# UI_Adapter.net
KiCad netlist of a schematic drawn in EAGLE
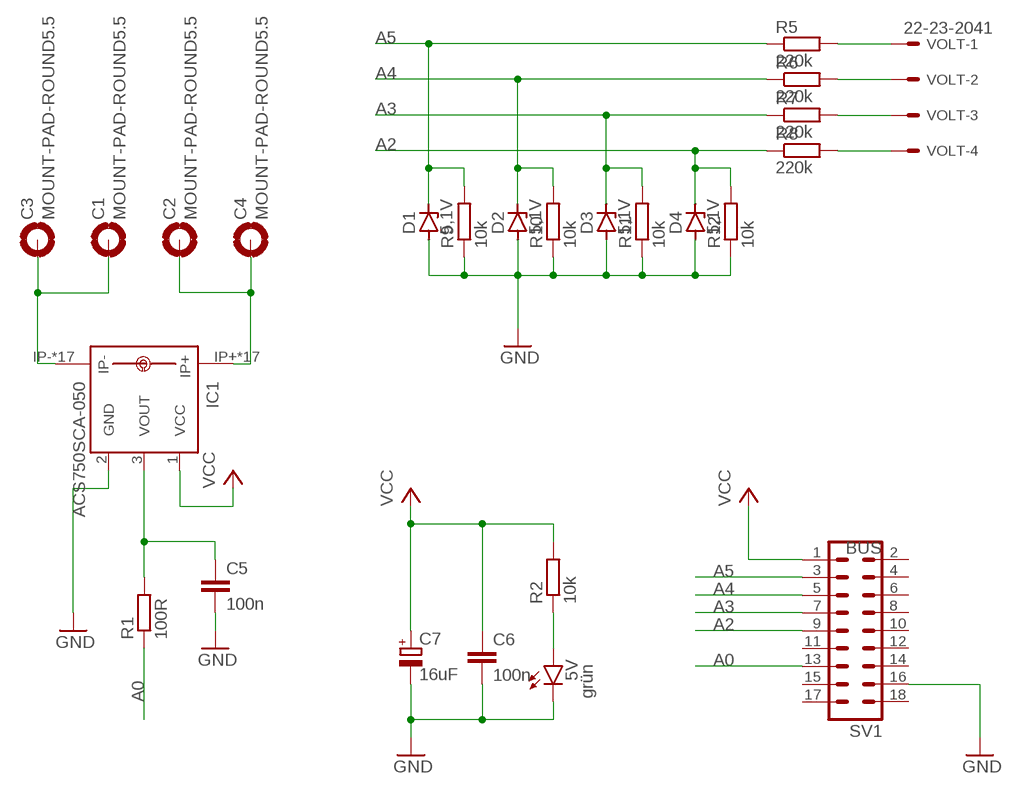
[diagram p0: schematic, sheet 1]

(export (version "E")
  (design (tool "Eeschema 10.0.6"))
  (components
    (comp (ref "5V")
      (value "grün")
      (footprint "eagle-import:LED3MM")
      (libsource (lib "eagle-import") (part "LED3MM"))
    )
    (comp (ref "C1")
      (value "MOUNT-PAD-ROUND5.5")
      (footprint "eagle-import:5,5-PAD")
      (libsource (lib "eagle-import") (part "MOUNT-PAD-ROUND5.5"))
    )
    (comp (ref "C2")
      (value "MOUNT-PAD-ROUND5.5")
      (footprint "eagle-import:5,5-PAD")
      (libsource (lib "eagle-import") (part "MOUNT-PAD-ROUND5.5"))
    )
    (comp (ref "C3")
      (value "MOUNT-PAD-ROUND5.5")
      (footprint "eagle-import:5,5-PAD")
      (libsource (lib "eagle-import") (part "MOUNT-PAD-ROUND5.5"))
    )
    (comp (ref "C4")
      (value "MOUNT-PAD-ROUND5.5")
      (footprint "eagle-import:5,5-PAD")
      (libsource (lib "eagle-import") (part "MOUNT-PAD-ROUND5.5"))
    )
    (comp (ref "C5")
      (value "100n")
      (footprint "eagle-import:C025-024X044")
      (libsource (lib "eagle-import") (part "C-EU025-024X044"))
    )
    (comp (ref "C6")
      (value "100n")
      (footprint "eagle-import:C025-024X044")
      (libsource (lib "eagle-import") (part "C-EU025-024X044"))
    )
    (comp (ref "C7")
      (value "16uF")
      (footprint "eagle-import:E2-5")
      (libsource (lib "eagle-import") (part "CPOL-EUE2-5"))
    )
    (comp (ref "D1")
      (value "5,1V")
      (footprint "eagle-import:ZDIO-7.5")
      (libsource (lib "eagle-import") (part "ZENER-DIODEZD-7.5"))
    )
    (comp (ref "D2")
      (value "5,1V")
      (footprint "eagle-import:ZDIO-7.5")
      (libsource (lib "eagle-import") (part "ZENER-DIODEZD-7.5"))
    )
    (comp (ref "D3")
      (value "5,1V")
      (footprint "eagle-import:ZDIO-7.5")
      (libsource (lib "eagle-import") (part "ZENER-DIODEZD-7.5"))
    )
    (comp (ref "D4")
      (value "5,1V")
      (footprint "eagle-import:ZDIO-7.5")
      (libsource (lib "eagle-import") (part "ZENER-DIODEZD-7.5"))
    )
    (comp (ref "IC1")
      (value "ACS750SCA-050")
      (footprint "eagle-import:ACS75050")
      (fields (field (name "MF") "ALLEGRO MICROSYSTEMS, INC."))
      (libsource (lib "eagle-import") (part "ACS750CA-050S"))
    )
    (comp (ref "R1")
      (value "100R")
      (footprint "eagle-import:0204V")
      (libsource (lib "eagle-import") (part "R-EU_0204/2V"))
    )
    (comp (ref "R2")
      (value "10k")
      (footprint "eagle-import:0204V")
      (libsource (lib "eagle-import") (part "R-EU_0204/2V"))
    )
    (comp (ref "R5")
      (value "220k")
      (footprint "eagle-import:0204V")
      (libsource (lib "eagle-import") (part "R-EU_0204/2V"))
    )
    (comp (ref "R6")
      (value "220k")
      (footprint "eagle-import:0204V")
      (libsource (lib "eagle-import") (part "R-EU_0204/2V"))
    )
    (comp (ref "R7")
      (value "220k")
      (footprint "eagle-import:0204V")
      (libsource (lib "eagle-import") (part "R-EU_0204/2V"))
    )
    (comp (ref "R8")
      (value "220k")
      (footprint "eagle-import:0204V")
      (libsource (lib "eagle-import") (part "R-EU_0204/2V"))
    )
    (comp (ref "R9")
      (value "10k")
      (footprint "eagle-import:0204V")
      (libsource (lib "eagle-import") (part "R-EU_0204/2V"))
    )
    (comp (ref "R10")
      (value "10k")
      (footprint "eagle-import:0204V")
      (libsource (lib "eagle-import") (part "R-EU_0204/2V"))
    )
    (comp (ref "R11")
      (value "10k")
      (footprint "eagle-import:0204V")
      (libsource (lib "eagle-import") (part "R-EU_0204/2V"))
    )
    (comp (ref "R12")
      (value "10k")
      (footprint "eagle-import:0204V")
      (libsource (lib "eagle-import") (part "R-EU_0204/2V"))
    )
    (comp (ref "SV1")
      (value "BUS")
      (footprint "eagle-import:MA09-2")
      (libsource (lib "eagle-import") (part "MA09-2"))
    )
    (comp (ref "VOLT")
      (value "22-23-2041")
      (footprint "eagle-import:22-23-2041")
      (fields (field (name "MF") "MOLEX"))
      (libsource (lib "eagle-import") (part "22-23-2041"))
    )
  )
  (nets
    (net (code "1") (name "A0") (class "Default")
      (node (ref "R1") (pin "1") (pinfunction "1_1") (pintype "passive"))
      (node (ref "SV1") (pin "13") (pinfunction "13_13") (pintype "passive"))
    )
    (net (code "2") (name "A2") (class "Default")
      (node (ref "D4") (pin "C") (pinfunction "C_C") (pintype "passive"))
      (node (ref "R12") (pin "2") (pinfunction "2_2") (pintype "passive"))
      (node (ref "R8") (pin "1") (pinfunction "1_1") (pintype "passive"))
      (node (ref "SV1") (pin "9") (pinfunction "9_9") (pintype "passive"))
    )
    (net (code "3") (name "A3") (class "Default")
      (node (ref "D3") (pin "C") (pinfunction "C_C") (pintype "passive"))
      (node (ref "R11") (pin "2") (pinfunction "2_2") (pintype "passive"))
      (node (ref "R7") (pin "1") (pinfunction "1_1") (pintype "passive"))
      (node (ref "SV1") (pin "7") (pinfunction "7_7") (pintype "passive"))
    )
    (net (code "4") (name "A4") (class "Default")
      (node (ref "D2") (pin "C") (pinfunction "C_C") (pintype "passive"))
      (node (ref "R10") (pin "2") (pinfunction "2_2") (pintype "passive"))
      (node (ref "R6") (pin "1") (pinfunction "1_1") (pintype "passive"))
      (node (ref "SV1") (pin "5") (pinfunction "5_5") (pintype "passive"))
    )
    (net (code "5") (name "A5") (class "Default")
      (node (ref "D1") (pin "C") (pinfunction "C_C") (pintype "passive"))
      (node (ref "R5") (pin "1") (pinfunction "1_1") (pintype "passive"))
      (node (ref "R9") (pin "2") (pinfunction "2_2") (pintype "passive"))
      (node (ref "SV1") (pin "3") (pinfunction "3_3") (pintype "passive"))
    )
    (net (code "6") (name "GND") (class "Default")
      (node (ref "5V") (pin "K") (pinfunction "C_K") (pintype "passive"))
      (node (ref "C5") (pin "2") (pinfunction "2_2") (pintype "passive"))
      (node (ref "C6") (pin "2") (pinfunction "2_2") (pintype "passive"))
      (node (ref "C7") (pin "-") (pinfunction "-_-") (pintype "passive"))
      (node (ref "D1") (pin "A") (pinfunction "A_A") (pintype "passive"))
      (node (ref "D2") (pin "A") (pinfunction "A_A") (pintype "passive"))
      (node (ref "D3") (pin "A") (pinfunction "A_A") (pintype "passive"))
      (node (ref "D4") (pin "A") (pinfunction "A_A") (pintype "passive"))
      (node (ref "IC1") (pin "2") (pinfunction "GND_2") (pintype "power_in"))
      (node (ref "R10") (pin "1") (pinfunction "1_1") (pintype "passive"))
      (node (ref "R11") (pin "1") (pinfunction "1_1") (pintype "passive"))
      (node (ref "R12") (pin "1") (pinfunction "1_1") (pintype "passive"))
      (node (ref "R9") (pin "1") (pinfunction "1_1") (pintype "passive"))
      (node (ref "SV1") (pin "16") (pinfunction "16_16") (pintype "passive"))
    )
    (net (code "7") (name "Net-(5V-PadA)") (class "Default")
      (node (ref "5V") (pin "A") (pinfunction "A_A") (pintype "passive"))
      (node (ref "R2") (pin "1") (pinfunction "1_1") (pintype "passive"))
    )
    (net (code "8") (name "Net-(C1-MOUNT)") (class "Default")
      (node (ref "C1") (pin "B5,5") (pinfunction "MOUNT_B5,5") (pintype "passive"))
      (node (ref "C3") (pin "B5,5") (pinfunction "MOUNT_B5,5") (pintype "passive"))
      (node (ref "IC1") (pin "IP-") (pinfunction "IP-_IP-") (pintype "passive"))
      (node (ref "IC1") (pin "IP-@10") (pinfunction "IP-_IP-@10") (pintype "passive"))
      (node (ref "IC1") (pin "IP-@11") (pinfunction "IP-_IP-@11") (pintype "passive"))
      (node (ref "IC1") (pin "IP-@12") (pinfunction "IP-_IP-@12") (pintype "passive"))
      (node (ref "IC1") (pin "IP-@13") (pinfunction "IP-_IP-@13") (pintype "passive"))
      (node (ref "IC1") (pin "IP-@14") (pinfunction "IP-_IP-@14") (pintype "passive"))
      (node (ref "IC1") (pin "IP-@15") (pinfunction "IP-_IP-@15") (pintype "passive"))
      (node (ref "IC1") (pin "IP-@16") (pinfunction "IP-_IP-@16") (pintype "passive"))
      (node (ref "IC1") (pin "IP-@17") (pinfunction "IP-_IP-@17") (pintype "passive"))
      (node (ref "IC1") (pin "IP-@2") (pinfunction "IP-_IP-@2") (pintype "passive"))
      (node (ref "IC1") (pin "IP-@3") (pinfunction "IP-_IP-@3") (pintype "passive"))
      (node (ref "IC1") (pin "IP-@4") (pinfunction "IP-_IP-@4") (pintype "passive"))
      (node (ref "IC1") (pin "IP-@5") (pinfunction "IP-_IP-@5") (pintype "passive"))
      (node (ref "IC1") (pin "IP-@6") (pinfunction "IP-_IP-@6") (pintype "passive"))
      (node (ref "IC1") (pin "IP-@7") (pinfunction "IP-_IP-@7") (pintype "passive"))
      (node (ref "IC1") (pin "IP-@8") (pinfunction "IP-_IP-@8") (pintype "passive"))
      (node (ref "IC1") (pin "IP-@9") (pinfunction "IP-_IP-@9") (pintype "passive"))
    )
    (net (code "9") (name "Net-(C2-MOUNT)") (class "Default")
      (node (ref "C2") (pin "B5,5") (pinfunction "MOUNT_B5,5") (pintype "passive"))
      (node (ref "C4") (pin "B5,5") (pinfunction "MOUNT_B5,5") (pintype "passive"))
      (node (ref "IC1") (pin "IP+") (pinfunction "IP+_IP+") (pintype "passive"))
      (node (ref "IC1") (pin "IP+@10") (pinfunction "IP+_IP+@10") (pintype "passive"))
      (node (ref "IC1") (pin "IP+@11") (pinfunction "IP+_IP+@11") (pintype "passive"))
      (node (ref "IC1") (pin "IP+@12") (pinfunction "IP+_IP+@12") (pintype "passive"))
      (node (ref "IC1") (pin "IP+@13") (pinfunction "IP+_IP+@13") (pintype "passive"))
      (node (ref "IC1") (pin "IP+@14") (pinfunction "IP+_IP+@14") (pintype "passive"))
      (node (ref "IC1") (pin "IP+@15") (pinfunction "IP+_IP+@15") (pintype "passive"))
      (node (ref "IC1") (pin "IP+@16") (pinfunction "IP+_IP+@16") (pintype "passive"))
      (node (ref "IC1") (pin "IP+@17") (pinfunction "IP+_IP+@17") (pintype "passive"))
      (node (ref "IC1") (pin "IP+@2") (pinfunction "IP+_IP+@2") (pintype "passive"))
      (node (ref "IC1") (pin "IP+@3") (pinfunction "IP+_IP+@3") (pintype "passive"))
      (node (ref "IC1") (pin "IP+@4") (pinfunction "IP+_IP+@4") (pintype "passive"))
      (node (ref "IC1") (pin "IP+@5") (pinfunction "IP+_IP+@5") (pintype "passive"))
      (node (ref "IC1") (pin "IP+@6") (pinfunction "IP+_IP+@6") (pintype "passive"))
      (node (ref "IC1") (pin "IP+@7") (pinfunction "IP+_IP+@7") (pintype "passive"))
      (node (ref "IC1") (pin "IP+@8") (pinfunction "IP+_IP+@8") (pintype "passive"))
      (node (ref "IC1") (pin "IP+@9") (pinfunction "IP+_IP+@9") (pintype "passive"))
    )
    (net (code "10") (name "Net-(IC1-VOUT)") (class "Default")
      (node (ref "C5") (pin "1") (pinfunction "1_1") (pintype "passive"))
      (node (ref "IC1") (pin "3") (pinfunction "VOUT_3") (pintype "output"))
      (node (ref "R1") (pin "2") (pinfunction "2_2") (pintype "passive"))
    )
    (net (code "11") (name "Net-(VOLTA-S)") (class "Default")
      (node (ref "R5") (pin "2") (pinfunction "2_2") (pintype "passive"))
      (node (ref "VOLT") (pin "1") (pinfunction "S_1") (pintype "passive"))
    )
    (net (code "12") (name "Net-(VOLTB-S)") (class "Default")
      (node (ref "R6") (pin "2") (pinfunction "2_2") (pintype "passive"))
      (node (ref "VOLT") (pin "2") (pinfunction "S_2") (pintype "passive"))
    )
    (net (code "13") (name "Net-(VOLTC-S)") (class "Default")
      (node (ref "R7") (pin "2") (pinfunction "2_2") (pintype "passive"))
      (node (ref "VOLT") (pin "3") (pinfunction "S_3") (pintype "passive"))
    )
    (net (code "14") (name "Net-(VOLTD-S)") (class "Default")
      (node (ref "R8") (pin "2") (pinfunction "2_2") (pintype "passive"))
      (node (ref "VOLT") (pin "4") (pinfunction "S_4") (pintype "passive"))
    )
    (net (code "15") (name "VCC") (class "Default")
      (node (ref "C6") (pin "1") (pinfunction "1_1") (pintype "passive"))
      (node (ref "C7") (pin "+") (pinfunction "+_+") (pintype "passive"))
      (node (ref "IC1") (pin "1") (pinfunction "VCC_1") (pintype "power_in"))
      (node (ref "R2") (pin "2") (pinfunction "2_2") (pintype "passive"))
      (node (ref "SV1") (pin "1") (pinfunction "1_1") (pintype "passive"))
    )
    (net (code "16") (name "unconnected-(SV1-Pad2)") (class "Default")
      (node (ref "SV1") (pin "2") (pinfunction "2_2") (pintype "passive"))
    )
    (net (code "17") (name "unconnected-(SV1-Pad4)") (class "Default")
      (node (ref "SV1") (pin "4") (pinfunction "4_4") (pintype "passive"))
    )
    (net (code "18") (name "unconnected-(SV1-Pad6)") (class "Default")
      (node (ref "SV1") (pin "6") (pinfunction "6_6") (pintype "passive"))
    )
    (net (code "19") (name "unconnected-(SV1-Pad8)") (class "Default")
      (node (ref "SV1") (pin "8") (pinfunction "8_8") (pintype "passive"))
    )
    (net (code "20") (name "unconnected-(SV1-Pad10)") (class "Default")
      (node (ref "SV1") (pin "10") (pinfunction "10_10") (pintype "passive"))
    )
    (net (code "21") (name "unconnected-(SV1-Pad11)") (class "Default")
      (node (ref "SV1") (pin "11") (pinfunction "11_11") (pintype "passive"))
    )
    (net (code "22") (name "unconnected-(SV1-Pad12)") (class "Default")
      (node (ref "SV1") (pin "12") (pinfunction "12_12") (pintype "passive"))
    )
    (net (code "23") (name "unconnected-(SV1-Pad14)") (class "Default")
      (node (ref "SV1") (pin "14") (pinfunction "14_14") (pintype "passive"))
    )
    (net (code "24") (name "unconnected-(SV1-Pad15)") (class "Default")
      (node (ref "SV1") (pin "15") (pinfunction "15_15") (pintype "passive"))
    )
    (net (code "25") (name "unconnected-(SV1-Pad17)") (class "Default")
      (node (ref "SV1") (pin "17") (pinfunction "17_17") (pintype "passive"))
    )
    (net (code "26") (name "unconnected-(SV1-Pad18)") (class "Default")
      (node (ref "SV1") (pin "18") (pinfunction "18_18") (pintype "passive"))
    )
  )
)
